# SipPuffDuoOutputsATtiny84Relays.net
KiCad netlist of a schematic drawn in EAGLE
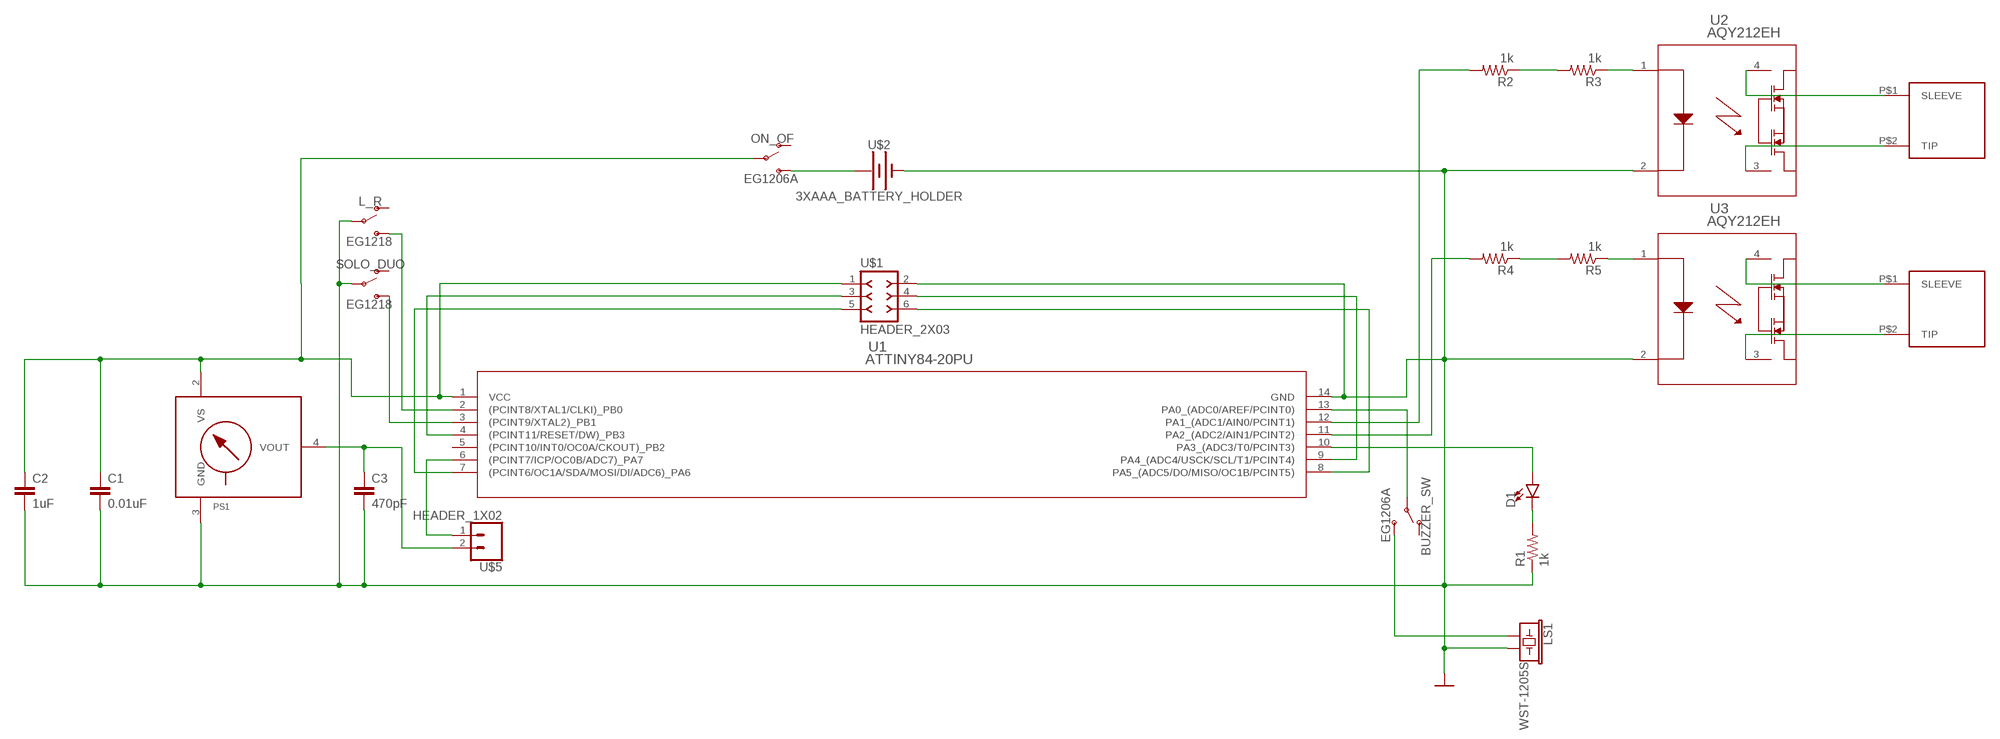
[diagram p0: schematic, sheet 1]

(export (version "E")
  (design (tool "Eeschema 10.0.6"))
  (components
    (comp (ref "BUZZER_SW")
      (value "EG1206A")
      (footprint "eagle-import:EG1206A")
      (libsource (lib "eagle-import") (part "EG1206A"))
    )
    (comp (ref "C1")
      (value "0.01uF")
      (footprint "eagle-import:CAP-PTH-SMALL-KIT")
      (libsource (lib "eagle-import") (part "0.1UF-KIT-EZ-50V-20%"))
    )
    (comp (ref "C2")
      (value "1uF")
      (footprint "eagle-import:CAP-PTH-SMALL-KIT")
      (libsource (lib "eagle-import") (part "0.1UF-KIT-EZ-50V-20%"))
    )
    (comp (ref "C3")
      (value "470pF")
      (footprint "eagle-import:CAP-PTH-SMALL-KIT")
      (libsource (lib "eagle-import") (part "0.1UF-KIT-EZ-50V-20%"))
    )
    (comp (ref "D1")
      (value "LED5MM")
      (footprint "eagle-import:LED_5MM")
      (libsource (lib "eagle-import") (part "LED5MM"))
    )
    (comp (ref "LS1")
      (value "WST-1205S")
      (footprint "eagle-import:BUZZER-12MM")
      (libsource (lib "eagle-import") (part "BUZZER-PTH"))
    )
    (comp (ref "L_R")
      (value "EG1218")
      (footprint "eagle-import:EG1218")
      (libsource (lib "eagle-import") (part "EG1218"))
    )
    (comp (ref "ON_OF")
      (value "EG1206A")
      (footprint "eagle-import:EG1206A")
      (libsource (lib "eagle-import") (part "EG1206A"))
    )
    (comp (ref "PS1")
      (value "MPX-1351")
      (footprint "eagle-import:1351")
      (libsource (lib "eagle-import") (part "MPX-1351"))
    )
    (comp (ref "R1")
      (value "1k")
      (footprint "eagle-import:RESISTOR_0207_10")
      (libsource (lib "eagle-import") (part "RESISTOR_R-US_"))
    )
    (comp (ref "R2")
      (value "1k")
      (footprint "eagle-import:RESISTOR_0207_10")
      (libsource (lib "eagle-import") (part "RESISTOR_R-US_"))
    )
    (comp (ref "R3")
      (value "1k")
      (footprint "eagle-import:RESISTOR_0207_10")
      (libsource (lib "eagle-import") (part "RESISTOR_R-US_"))
    )
    (comp (ref "R4")
      (value "1k")
      (footprint "eagle-import:RESISTOR_0207_10")
      (libsource (lib "eagle-import") (part "RESISTOR_R-US_"))
    )
    (comp (ref "R5")
      (value "1k")
      (footprint "eagle-import:RESISTOR_0207_10")
      (libsource (lib "eagle-import") (part "RESISTOR_R-US_"))
    )
    (comp (ref "SOLO_DUO")
      (value "EG1218")
      (footprint "eagle-import:EG1218")
      (libsource (lib "eagle-import") (part "EG1218"))
    )
    (comp (ref "U$1")
      (value "HEADER_2X03")
      (footprint "eagle-import:2X3")
      (libsource (lib "eagle-import") (part "HEADER_2X03"))
    )
    (comp (ref "U$2")
      (value "3XAAA_BATTERY_HOLDER")
      (footprint "eagle-import:3XAAA_BATTERY_HOLDER")
      (libsource (lib "eagle-import") (part "3XAAA_BATTERY_HOLDER"))
    )
    (comp (ref "U$3")
      (value "MONO_WIRE")
      (footprint "eagle-import:MONO_WIRE")
      (libsource (lib "eagle-import") (part "MONO_WIRE"))
    )
    (comp (ref "U$4")
      (value "MONO_WIRE")
      (footprint "eagle-import:MONO_WIRE")
      (libsource (lib "eagle-import") (part "MONO_WIRE"))
    )
    (comp (ref "U$5")
      (value "HEADER_1X02")
      (footprint "eagle-import:1X02")
      (libsource (lib "eagle-import") (part "HEADER_1X02"))
    )
    (comp (ref "U1")
      (value "ATTINY84-20PU")
      (footprint "eagle-import:14P3")
      (fields (field (name "MANUFACTURER_PART_NUMBER") "ATTINY8420PU"))
      (libsource (lib "eagle-import") (part "ATTINY84-20PU"))
    )
    (comp (ref "U2")
      (value "AQY212EH")
      (footprint "eagle-import:PAN_AQY21-DIP4")
      (libsource (lib "eagle-import") (part "AQY212EH"))
    )
    (comp (ref "U3")
      (value "AQY212EH")
      (footprint "eagle-import:PAN_AQY21-DIP4")
      (libsource (lib "eagle-import") (part "AQY212EH"))
    )
  )
  (nets
    (net (code "1") (name "GND") (class "Default")
      (node (ref "C1") (pin "2") (pinfunction "2_2") (pintype "passive"))
      (node (ref "C2") (pin "2") (pinfunction "2_2") (pintype "passive"))
      (node (ref "C3") (pin "2") (pinfunction "2_2") (pintype "passive"))
      (node (ref "LS1") (pin "-") (pinfunction "2_-") (pintype "passive"))
      (node (ref "L_R") (pin "2") (pinfunction "P_2") (pintype "passive"))
      (node (ref "PS1") (pin "3") (pinfunction "GND_3") (pintype "power_in"))
      (node (ref "R1") (pin "1") (pinfunction "1_1") (pintype "passive"))
      (node (ref "SOLO_DUO") (pin "2") (pinfunction "P_2") (pintype "passive"))
      (node (ref "U$1") (pin "2") (pinfunction "2_2") (pintype "passive"))
      (node (ref "U$2") (pin "P$2") (pinfunction "-_P$2") (pintype "power_in"))
      (node (ref "U1") (pin "14") (pinfunction "GND_14") (pintype "power_in"))
      (node (ref "U2") (pin "2") (pinfunction "2_2") (pintype "passive"))
      (node (ref "U3") (pin "2") (pinfunction "2_2") (pintype "passive"))
    )
    (net (code "2") (name "Net-(BUZZER_SW-P)") (class "Default")
      (node (ref "BUZZER_SW") (pin "2") (pinfunction "P_2") (pintype "passive"))
      (node (ref "U1") (pin "13") (pinfunction "PA0_(ADC0/AREF/PCINT0)_13") (pintype "bidirectional"))
    )
    (net (code "3") (name "Net-(BUZZER_SW-S)") (class "Default")
      (node (ref "BUZZER_SW") (pin "3") (pinfunction "S_3") (pintype "passive"))
      (node (ref "LS1") (pin "+") (pinfunction "1_+") (pintype "passive"))
    )
    (net (code "4") (name "Net-(D1-C)") (class "Default")
      (node (ref "D1") (pin "K") (pinfunction "C_K") (pintype "passive"))
      (node (ref "R1") (pin "2") (pinfunction "2_2") (pintype "passive"))
    )
    (net (code "5") (name "Net-(L_R-S)") (class "Default")
      (node (ref "L_R") (pin "3") (pinfunction "S_3") (pintype "passive"))
      (node (ref "U1") (pin "2") (pinfunction "(PCINT8/XTAL1/CLKI)_PB0_2") (pintype "bidirectional"))
    )
    (net (code "6") (name "Net-(ON_OF-P)") (class "Default")
      (node (ref "C1") (pin "1") (pinfunction "1_1") (pintype "passive"))
      (node (ref "C2") (pin "1") (pinfunction "1_1") (pintype "passive"))
      (node (ref "ON_OF") (pin "2") (pinfunction "P_2") (pintype "passive"))
      (node (ref "PS1") (pin "2") (pinfunction "VS_2") (pintype "power_in"))
      (node (ref "U$1") (pin "1") (pinfunction "1_1") (pintype "passive"))
      (node (ref "U1") (pin "1") (pinfunction "VCC_1") (pintype "power_in"))
    )
    (net (code "7") (name "Net-(ON_OF-S)") (class "Default")
      (node (ref "ON_OF") (pin "3") (pinfunction "S_3") (pintype "passive"))
      (node (ref "U$2") (pin "P$1") (pinfunction "+_P$1") (pintype "power_in"))
    )
    (net (code "8") (name "Net-(PS1-VOUT)") (class "Default")
      (node (ref "C3") (pin "1") (pinfunction "1_1") (pintype "passive"))
      (node (ref "PS1") (pin "4") (pinfunction "VOUT_4") (pintype "output"))
      (node (ref "U$5") (pin "2") (pinfunction "2_2") (pintype "passive"))
    )
    (net (code "9") (name "Net-(R2-Pad1)") (class "Default")
      (node (ref "R2") (pin "1") (pinfunction "1_1") (pintype "passive"))
      (node (ref "R3") (pin "2") (pinfunction "2_2") (pintype "passive"))
    )
    (net (code "10") (name "Net-(R3-Pad1)") (class "Default")
      (node (ref "R3") (pin "1") (pinfunction "1_1") (pintype "passive"))
      (node (ref "U2") (pin "1") (pinfunction "1_1") (pintype "passive"))
    )
    (net (code "11") (name "Net-(R4-Pad1)") (class "Default")
      (node (ref "R4") (pin "1") (pinfunction "1_1") (pintype "passive"))
      (node (ref "R5") (pin "2") (pinfunction "2_2") (pintype "passive"))
    )
    (net (code "12") (name "Net-(R5-Pad1)") (class "Default")
      (node (ref "R5") (pin "1") (pinfunction "1_1") (pintype "passive"))
      (node (ref "U3") (pin "1") (pinfunction "1_1") (pintype "passive"))
    )
    (net (code "13") (name "Net-(SOLO_DUO-S)") (class "Default")
      (node (ref "SOLO_DUO") (pin "3") (pinfunction "S_3") (pintype "passive"))
      (node (ref "U1") (pin "3") (pinfunction "(PCINT9/XTAL2)_PB1_3") (pintype "bidirectional"))
    )
    (net (code "14") (name "Net-(U$3-SLEEVE)") (class "Default")
      (node (ref "U$3") (pin "P$1") (pinfunction "SLEEVE_P$1") (pintype "bidirectional"))
      (node (ref "U2") (pin "4") (pinfunction "4_4") (pintype "passive"))
    )
    (net (code "15") (name "Net-(U$3-TIP)") (class "Default")
      (node (ref "U$3") (pin "P$2") (pinfunction "TIP_P$2") (pintype "bidirectional"))
      (node (ref "U2") (pin "3") (pinfunction "3_3") (pintype "passive"))
    )
    (net (code "16") (name "Net-(U$4-SLEEVE)") (class "Default")
      (node (ref "U$4") (pin "P$1") (pinfunction "SLEEVE_P$1") (pintype "bidirectional"))
      (node (ref "U3") (pin "4") (pinfunction "4_4") (pintype "passive"))
    )
    (net (code "17") (name "Net-(U$4-TIP)") (class "Default")
      (node (ref "U$4") (pin "P$2") (pinfunction "TIP_P$2") (pintype "bidirectional"))
      (node (ref "U3") (pin "3") (pinfunction "3_3") (pintype "passive"))
    )
    (net (code "18") (name "Net-(U1-(PCINT6{slash}OC1A{slash}SDA{slash}MOSI{slash}DI{slash}ADC6)_PA6)") (class "Default")
      (node (ref "U$1") (pin "5") (pinfunction "5_5") (pintype "passive"))
      (node (ref "U1") (pin "7") (pinfunction "(PCINT6/OC1A/SDA/MOSI/DI/ADC6)_PA6_7") (pintype "bidirectional"))
    )
    (net (code "19") (name "Net-(U1-(PCINT7{slash}ICP{slash}OC0B{slash}ADC7)_PA7)") (class "Default")
      (node (ref "U$5") (pin "1") (pinfunction "1_1") (pintype "passive"))
      (node (ref "U1") (pin "6") (pinfunction "(PCINT7/ICP/OC0B/ADC7)_PA7_6") (pintype "bidirectional"))
    )
    (net (code "20") (name "Net-(U1-(PCINT11{slash}RESET{slash}DW)_PB3)") (class "Default")
      (node (ref "U$1") (pin "3") (pinfunction "3_3") (pintype "passive"))
      (node (ref "U1") (pin "4") (pinfunction "(PCINT11/RESET/DW)_PB3_4") (pintype "bidirectional"))
    )
    (net (code "21") (name "Net-(U1-PA1_(ADC1{slash}AIN0{slash}PCINT1))") (class "Default")
      (node (ref "R2") (pin "2") (pinfunction "2_2") (pintype "passive"))
      (node (ref "U1") (pin "12") (pinfunction "PA1_(ADC1/AIN0/PCINT1)_12") (pintype "bidirectional"))
    )
    (net (code "22") (name "Net-(U1-PA2_(ADC2{slash}AIN1{slash}PCINT2))") (class "Default")
      (node (ref "R4") (pin "2") (pinfunction "2_2") (pintype "passive"))
      (node (ref "U1") (pin "11") (pinfunction "PA2_(ADC2/AIN1/PCINT2)_11") (pintype "bidirectional"))
    )
    (net (code "23") (name "Net-(U1-PA3_(ADC3{slash}T0{slash}PCINT3))") (class "Default")
      (node (ref "D1") (pin "A") (pinfunction "A_A") (pintype "passive"))
      (node (ref "U1") (pin "10") (pinfunction "PA3_(ADC3/T0/PCINT3)_10") (pintype "bidirectional"))
    )
    (net (code "24") (name "Net-(U1-PA4_(ADC4{slash}USCK{slash}SCL{slash}T1{slash}PCINT4))") (class "Default")
      (node (ref "U$1") (pin "4") (pinfunction "4_4") (pintype "passive"))
      (node (ref "U1") (pin "9") (pinfunction "PA4_(ADC4/USCK/SCL/T1/PCINT4)_9") (pintype "bidirectional"))
    )
    (net (code "25") (name "Net-(U1-PA5_(ADC5{slash}DO{slash}MISO{slash}OC1B{slash}PCINT5))") (class "Default")
      (node (ref "U$1") (pin "6") (pinfunction "6_6") (pintype "passive"))
      (node (ref "U1") (pin "8") (pinfunction "PA5_(ADC5/DO/MISO/OC1B/PCINT5)_8") (pintype "bidirectional"))
    )
    (net (code "26") (name "unconnected-(BUZZER_SW-O-Pad1)") (class "Default")
      (node (ref "BUZZER_SW") (pin "1") (pinfunction "O_1") (pintype "passive"))
    )
    (net (code "27") (name "unconnected-(L_R-O-Pad1)") (class "Default")
      (node (ref "L_R") (pin "1") (pinfunction "O_1") (pintype "passive"))
    )
    (net (code "28") (name "unconnected-(ON_OF-O-Pad1)") (class "Default")
      (node (ref "ON_OF") (pin "1") (pinfunction "O_1") (pintype "passive"))
    )
    (net (code "29") (name "unconnected-(PS1-NC-Pad1)") (class "Default")
      (node (ref "PS1") (pin "1") (pinfunction "NC_1") (pintype "no_connect"))
    )
    (net (code "30") (name "unconnected-(PS1-NC-Pad5)") (class "Default")
      (node (ref "PS1") (pin "5") (pinfunction "NC_5") (pintype "no_connect"))
    )
    (net (code "31") (name "unconnected-(PS1-NC-Pad6)") (class "Default")
      (node (ref "PS1") (pin "6") (pinfunction "NC_6") (pintype "no_connect"))
    )
    (net (code "32") (name "unconnected-(SOLO_DUO-O-Pad1)") (class "Default")
      (node (ref "SOLO_DUO") (pin "1") (pinfunction "O_1") (pintype "passive"))
    )
    (net (code "33") (name "unconnected-(U1-(PCINT10{slash}INT0{slash}OC0A{slash}CKOUT)_PB2-Pad5)") (class "Default")
      (node (ref "U1") (pin "5") (pinfunction "(PCINT10/INT0/OC0A/CKOUT)_PB2_5") (pintype "bidirectional"))
    )
  )
)
